# MR_UartConnector.net
KiCad netlist of a schematic drawn in Altium Designer
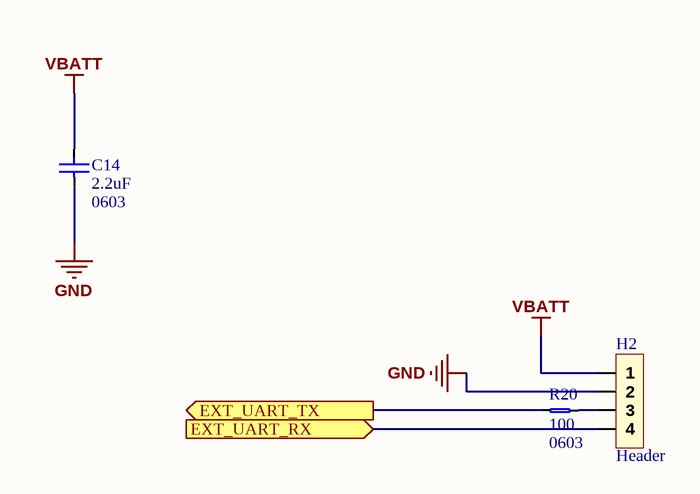
[diagram p0: MR_UartConnector.SchDoc]

(export (version "E")
  (design (tool "Eeschema 10.0.6"))
  (components
    (comp (ref "C14")
      (value "2.2uF")
      (footprint "0603_CAP_LD")
      (description "Ceramic Capacitor")
      (fields (field (name "PACKAGE") "0603") (field (name "Comment") "CerCap"))
      (libsource (lib "MiniRobot") (part "CerCap"))
    )
    (comp (ref "H2")
      (value "Header")
      (footprint "HE14 1x4 Straight")
      (description "Header 4x1 PIns")
      (libsource (lib "MiniRobot") (part "Header_4x1"))
    )
    (comp (ref "R20")
      (value "100")
      (footprint "0603_RES_LD")
      (description "Resistor")
      (fields (field (name "PACKAGE") "0603"))
      (libsource (lib "MiniRobot") (part "Resistor"))
    )
  )
  (nets
    (net (code "1") (name "/EXT_UART_RX") (class "Default")
      (node (ref "H2") (pin "4") (pinfunction "4_4") (pintype "passive"))
    )
    (net (code "2") (name "/EXT_UART_TX") (class "Default")
      (node (ref "R20") (pin "1") (pinfunction "1_1") (pintype "passive"))
    )
    (net (code "3") (name "GND") (class "Default")
      (node (ref "C14") (pin "1") (pinfunction "1_1") (pintype "passive"))
      (node (ref "H2") (pin "2") (pinfunction "2_2") (pintype "passive"))
    )
    (net (code "4") (name "Net-(H2-Pad3)") (class "Default")
      (node (ref "H2") (pin "3") (pinfunction "3_3") (pintype "passive"))
      (node (ref "R20") (pin "2") (pinfunction "2_2") (pintype "passive"))
    )
    (net (code "5") (name "VBATT") (class "Default")
      (node (ref "C14") (pin "2") (pinfunction "2_2") (pintype "passive"))
      (node (ref "H2") (pin "1") (pinfunction "1_1") (pintype "passive"))
    )
  )
)
